# MEGA_MSX_A.net
KiCad netlist of a schematic drawn in EAGLE
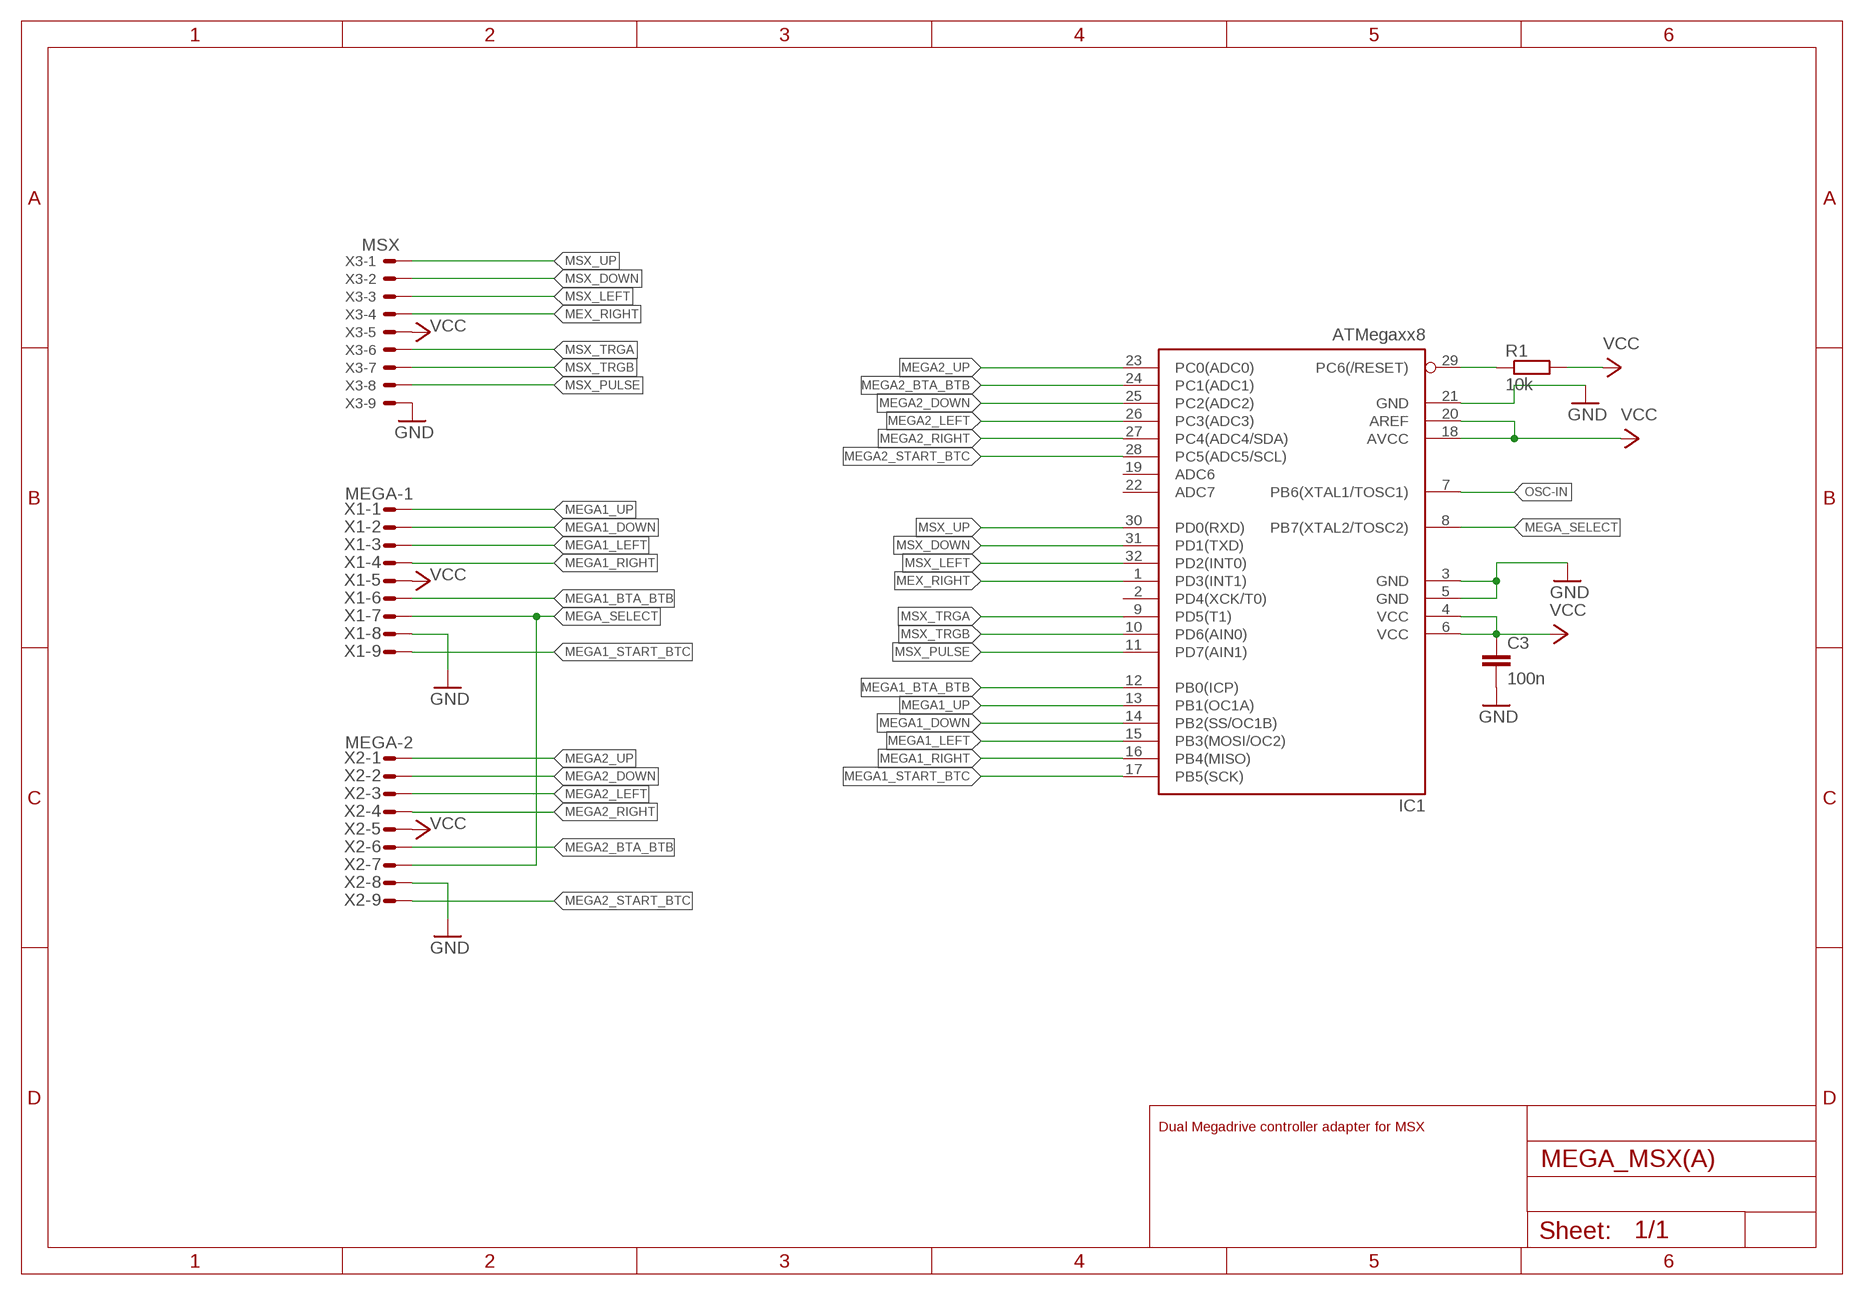
[diagram p0: schematic, sheet 1]

(export (version "E")
  (design (tool "Eeschema 10.0.6"))
  (components
    (comp (ref "C3")
      (value "100n")
      (footprint "eagle-import:C0805")
      (libsource (lib "eagle-import") (part "C-EUC0805"))
    )
    (comp (ref "IC1")
      (value "ATMegaxx8")
      (footprint "eagle-import:TQFP32-08")
      (fields (field (name "MPN") "ATMEGA8-16AU"))
      (libsource (lib "eagle-import") (part "MEGA8-AI"))
    )
    (comp (ref "R1")
      (value "10k")
      (footprint "eagle-import:R0805")
      (libsource (lib "eagle-import") (part "R-EU_R0805"))
    )
    (comp (ref "X1")
      (value "MEGA-1")
      (footprint "eagle-import:M09D")
      (libsource (lib "eagle-import") (part "M09?SD"))
    )
    (comp (ref "X2")
      (value "MEGA-2")
      (footprint "eagle-import:M09D")
      (libsource (lib "eagle-import") (part "M09?SD"))
    )
    (comp (ref "X3")
      (value "MSX")
      (footprint "eagle-import:22-23-2091")
      (fields (field (name "MF") "MOLEX") (field (name "MPN") "22-23-2091"))
      (libsource (lib "eagle-import") (part "22-23-2091"))
    )
  )
  (nets
    (net (code "1") (name "GND") (class "Default")
      (node (ref "C3") (pin "2") (pinfunction "2_2") (pintype "passive"))
      (node (ref "IC1") (pin "21") (pinfunction "GND_21") (pintype "power_in"))
      (node (ref "IC1") (pin "3") (pinfunction "GND_3") (pintype "power_in"))
      (node (ref "IC1") (pin "5") (pinfunction "GND_5") (pintype "power_in"))
      (node (ref "X1") (pin "8") (pinfunction "M_8") (pintype "passive"))
      (node (ref "X2") (pin "8") (pinfunction "M_8") (pintype "passive"))
      (node (ref "X3") (pin "9") (pinfunction "S_9") (pintype "passive"))
    )
    (net (code "2") (name "MEGA1_BTA_BTB") (class "Default")
      (node (ref "IC1") (pin "12") (pinfunction "PB0(ICP)_12") (pintype "bidirectional"))
      (node (ref "X1") (pin "6") (pinfunction "M_6") (pintype "passive"))
    )
    (net (code "3") (name "MEGA1_DOWN") (class "Default")
      (node (ref "IC1") (pin "14") (pinfunction "PB2(SS/OC1B)_14") (pintype "bidirectional"))
      (node (ref "X1") (pin "2") (pinfunction "M_2") (pintype "passive"))
    )
    (net (code "4") (name "MEGA1_LEFT") (class "Default")
      (node (ref "IC1") (pin "15") (pinfunction "PB3(MOSI/OC2)_15") (pintype "bidirectional"))
      (node (ref "X1") (pin "3") (pinfunction "M_3") (pintype "passive"))
    )
    (net (code "5") (name "MEGA1_RIGHT") (class "Default")
      (node (ref "IC1") (pin "16") (pinfunction "PB4(MISO)_16") (pintype "bidirectional"))
      (node (ref "X1") (pin "4") (pinfunction "M_4") (pintype "passive"))
    )
    (net (code "6") (name "MEGA1_START_BTC") (class "Default")
      (node (ref "IC1") (pin "17") (pinfunction "PB5(SCK)_17") (pintype "bidirectional"))
      (node (ref "X1") (pin "9") (pinfunction "M_9") (pintype "passive"))
    )
    (net (code "7") (name "MEGA1_UP") (class "Default")
      (node (ref "IC1") (pin "13") (pinfunction "PB1(OC1A)_13") (pintype "bidirectional"))
      (node (ref "X1") (pin "1") (pinfunction "M_1") (pintype "passive"))
    )
    (net (code "8") (name "MEGA2_BTA_BTB") (class "Default")
      (node (ref "IC1") (pin "24") (pinfunction "PC1(ADC1)_24") (pintype "bidirectional"))
      (node (ref "X2") (pin "6") (pinfunction "M_6") (pintype "passive"))
    )
    (net (code "9") (name "MEGA2_DOWN") (class "Default")
      (node (ref "IC1") (pin "25") (pinfunction "PC2(ADC2)_25") (pintype "bidirectional"))
      (node (ref "X2") (pin "2") (pinfunction "M_2") (pintype "passive"))
    )
    (net (code "10") (name "MEGA2_LEFT") (class "Default")
      (node (ref "IC1") (pin "26") (pinfunction "PC3(ADC3)_26") (pintype "bidirectional"))
      (node (ref "X2") (pin "3") (pinfunction "M_3") (pintype "passive"))
    )
    (net (code "11") (name "MEGA2_RIGHT") (class "Default")
      (node (ref "IC1") (pin "27") (pinfunction "PC4(ADC4/SDA)_27") (pintype "bidirectional"))
      (node (ref "X2") (pin "4") (pinfunction "M_4") (pintype "passive"))
    )
    (net (code "12") (name "MEGA2_START_BTC") (class "Default")
      (node (ref "IC1") (pin "28") (pinfunction "PC5(ADC5/SCL)_28") (pintype "bidirectional"))
      (node (ref "X2") (pin "9") (pinfunction "M_9") (pintype "passive"))
    )
    (net (code "13") (name "MEGA2_UP") (class "Default")
      (node (ref "IC1") (pin "23") (pinfunction "PC0(ADC0)_23") (pintype "bidirectional"))
      (node (ref "X2") (pin "1") (pinfunction "M_1") (pintype "passive"))
    )
    (net (code "14") (name "MEGA_SELECT") (class "Default")
      (node (ref "IC1") (pin "8") (pinfunction "PB7(XTAL2/TOSC2)_8") (pintype "bidirectional"))
      (node (ref "X1") (pin "7") (pinfunction "M_7") (pintype "passive"))
      (node (ref "X2") (pin "7") (pinfunction "M_7") (pintype "passive"))
    )
    (net (code "15") (name "MEX_RIGHT") (class "Default")
      (node (ref "IC1") (pin "1") (pinfunction "PD3(INT1)_1") (pintype "bidirectional"))
      (node (ref "X3") (pin "4") (pinfunction "S_4") (pintype "passive"))
    )
    (net (code "16") (name "MSX_DOWN") (class "Default")
      (node (ref "IC1") (pin "31") (pinfunction "PD1(TXD)_31") (pintype "bidirectional"))
      (node (ref "X3") (pin "2") (pinfunction "S_2") (pintype "passive"))
    )
    (net (code "17") (name "MSX_LEFT") (class "Default")
      (node (ref "IC1") (pin "32") (pinfunction "PD2(INT0)_32") (pintype "bidirectional"))
      (node (ref "X3") (pin "3") (pinfunction "S_3") (pintype "passive"))
    )
    (net (code "18") (name "MSX_PULSE") (class "Default")
      (node (ref "IC1") (pin "11") (pinfunction "PD7(AIN1)_11") (pintype "bidirectional"))
      (node (ref "X3") (pin "8") (pinfunction "S_8") (pintype "passive"))
    )
    (net (code "19") (name "MSX_TRGA") (class "Default")
      (node (ref "IC1") (pin "9") (pinfunction "PD5(T1)_9") (pintype "bidirectional"))
      (node (ref "X3") (pin "6") (pinfunction "S_6") (pintype "passive"))
    )
    (net (code "20") (name "MSX_TRGB") (class "Default")
      (node (ref "IC1") (pin "10") (pinfunction "PD6(AIN0)_10") (pintype "bidirectional"))
      (node (ref "X3") (pin "7") (pinfunction "S_7") (pintype "passive"))
    )
    (net (code "21") (name "MSX_UP") (class "Default")
      (node (ref "IC1") (pin "30") (pinfunction "PD0(RXD)_30") (pintype "bidirectional"))
      (node (ref "X3") (pin "1") (pinfunction "S_1") (pintype "passive"))
    )
    (net (code "22") (name "Net-(IC1-PC6({slash}RESET))") (class "Default")
      (node (ref "IC1") (pin "29") (pinfunction "PC6(/RESET)_29") (pintype "bidirectional"))
      (node (ref "R1") (pin "1") (pinfunction "1_1") (pintype "passive"))
    )
    (net (code "23") (name "OSC-IN") (class "Default")
      (node (ref "IC1") (pin "7") (pinfunction "PB6(XTAL1/TOSC1)_7") (pintype "bidirectional"))
    )
    (net (code "24") (name "VCC") (class "Default")
      (node (ref "C3") (pin "1") (pinfunction "1_1") (pintype "passive"))
      (node (ref "IC1") (pin "18") (pinfunction "AVCC_18") (pintype "power_in"))
      (node (ref "IC1") (pin "20") (pinfunction "AREF_20") (pintype "passive"))
      (node (ref "IC1") (pin "4") (pinfunction "VCC_4") (pintype "power_in"))
      (node (ref "IC1") (pin "6") (pinfunction "VCC_6") (pintype "power_in"))
      (node (ref "R1") (pin "2") (pinfunction "2_2") (pintype "passive"))
      (node (ref "X1") (pin "5") (pinfunction "M_5") (pintype "passive"))
      (node (ref "X2") (pin "5") (pinfunction "M_5") (pintype "passive"))
      (node (ref "X3") (pin "5") (pinfunction "S_5") (pintype "passive"))
    )
    (net (code "25") (name "unconnected-(IC1-ADC6-Pad19)") (class "Default")
      (node (ref "IC1") (pin "19") (pinfunction "ADC6_19") (pintype "bidirectional"))
    )
    (net (code "26") (name "unconnected-(IC1-ADC7-Pad22)") (class "Default")
      (node (ref "IC1") (pin "22") (pinfunction "ADC7_22") (pintype "bidirectional"))
    )
    (net (code "27") (name "unconnected-(IC1-PD4(XCK{slash}T0)-Pad2)") (class "Default")
      (node (ref "IC1") (pin "2") (pinfunction "PD4(XCK/T0)_2") (pintype "bidirectional"))
    )
  )
)
